# SAM9X75_Pinout.net
KiCad netlist of a schematic drawn in Altium Designer
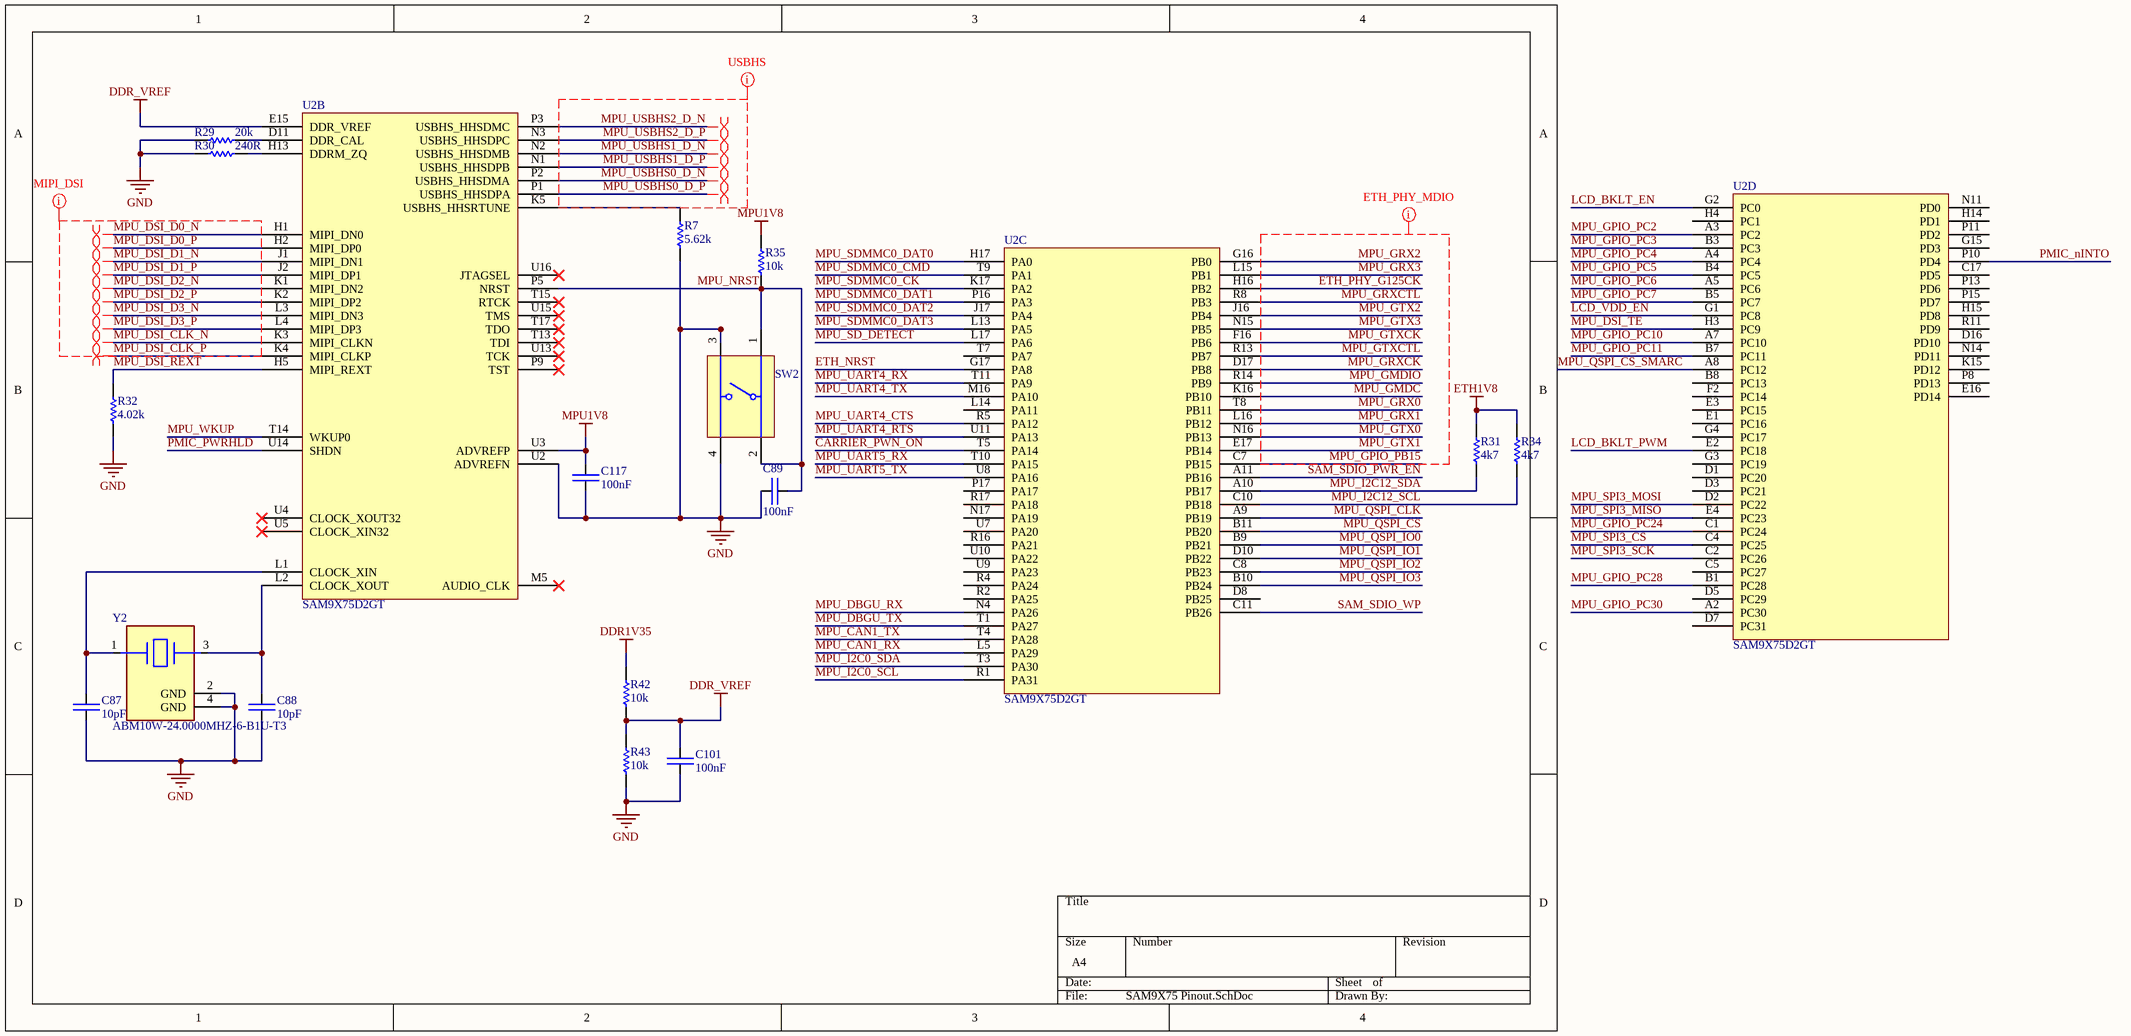
[diagram p0: SAM9X75 Pinout.SchDoc]

(export (version "E")
  (design (tool "Eeschema 10.0.6"))
  (components
    (comp (ref "C87")
      (value "10pF")
      (footprint "CAP-0603")
      (description "Capacitor chip unpolarized. 0603")
      (libsource (lib "Master") (part "CAP-0603"))
    )
    (comp (ref "C88")
      (value "10pF")
      (footprint "CAP-0603")
      (description "Capacitor chip unpolarized. 0603")
      (libsource (lib "Master") (part "CAP-0603"))
    )
    (comp (ref "C89")
      (value "100nF")
      (footprint "CAP-0603")
      (description "Capacitor chip unpolarized. 0603")
      (libsource (lib "Master") (part "CAP-0603"))
    )
    (comp (ref "C101")
      (value "100nF")
      (footprint "CAP-0201")
      (description "Capacitor chip upolarized. 0201")
      (libsource (lib "Master") (part "CAP-0201"))
    )
    (comp (ref "C117")
      (value "100nF")
      (footprint "CAP-0201")
      (description "Capacitor chip upolarized. 0201")
      (libsource (lib "Master") (part "CAP-0201"))
    )
    (comp (ref "R7")
      (value "5.62k")
      (footprint "RES-0201")
      (description "Resistor chip. 0201")
      (libsource (lib "Master") (part "RES-0201"))
    )
    (comp (ref "R29")
      (value "20k")
      (footprint "RES-0201")
      (description "Resistor chip. 0201")
      (libsource (lib "Master") (part "RES-0201"))
    )
    (comp (ref "R30")
      (value "240R")
      (footprint "RES-0201")
      (description "Resistor chip. 0201")
      (libsource (lib "Master") (part "RES-0201"))
    )
    (comp (ref "R31")
      (value "4k7")
      (footprint "RES-0201")
      (description "Resistor chip. 0201")
      (libsource (lib "Master") (part "RES-0201"))
    )
    (comp (ref "R32")
      (value "4.02k")
      (footprint "RES-0201")
      (description "Resistor chip. 0201")
      (libsource (lib "Master") (part "RES-0201"))
    )
    (comp (ref "R34")
      (value "4k7")
      (footprint "RES-0201")
      (description "Resistor chip. 0201")
      (libsource (lib "Master") (part "RES-0201"))
    )
    (comp (ref "R35")
      (value "10k")
      (footprint "RES-0603")
      (description "Resistor chip. 0603")
      (libsource (lib "Master") (part "RES-0603"))
    )
    (comp (ref "R42")
      (value "10k")
      (footprint "RES-0201")
      (description "Resistor chip. 0201")
      (libsource (lib "Master") (part "RES-0201"))
    )
    (comp (ref "R43")
      (value "10k")
      (footprint "RES-0201")
      (description "Resistor chip. 0201")
      (libsource (lib "Master") (part "RES-0201"))
    )
    (comp (ref "SW2")
      (value "FSM4JSMATR")
      (footprint "TECO-FSM4JSMATR_V")
      (description "Micro Miniature Push Button Switch FSM JSM, 50 mA, -35 to 85 degC, 4-Pin SMD, RoHS, Tape and Reel")
      (fields (field (name "MANUFACTURER") "TE Connectivity"))
      (libsource (lib "Altium Content Vault") (part "SW-SPST-4_A"))
    )
    (comp (ref "U2")
      (value "SAM9X75D2GT")
      (footprint "SAM9X75D")
      (description "ARM9 SiP 2GBit Internal DDR3L")
      (libsource (lib "Master") (part "SAM9X75D2GT"))
    )
    (comp (ref "Y2")
      (value "ABM10W-24.0000MHZ-6-B1U-T3")
      (footprint "FP-ABM10W-MFG")
      (description "Crystal 24MHz ±10ppm 6pF SMD-4 2.5mm x 2mm")
      (libsource (lib "Altium Content Vault") (part "5d53a81b36bb19e40e9e80ec3e46f97"))
    )
  )
  (nets
    (net (code "1") (name "/CARRIER_PWN_ON") (class "Default")
      (node (ref "U2") (pin "T5") (pinfunction "PA14_T5") (pintype "passive"))
    )
    (net (code "2") (name "/ETH_NRST") (class "Default")
      (node (ref "U2") (pin "G17") (pinfunction "PA8_G17") (pintype "passive"))
    )
    (net (code "3") (name "/ETH_PHY_G125CK") (class "Default")
      (node (ref "U2") (pin "H16") (pinfunction "PB2_H16") (pintype "passive"))
    )
    (net (code "4") (name "/LCD_BKLT_EN") (class "Default")
      (node (ref "U2") (pin "G2") (pinfunction "PC0_G2") (pintype "passive"))
    )
    (net (code "5") (name "/LCD_BKLT_PWM") (class "Default")
      (node (ref "U2") (pin "E2") (pinfunction "PC18_E2") (pintype "passive"))
    )
    (net (code "6") (name "/LCD_VDD_EN") (class "Default")
      (node (ref "U2") (pin "G1") (pinfunction "PC8_G1") (pintype "passive"))
    )
    (net (code "7") (name "/MPU_CAN1_RX") (class "Default")
      (node (ref "U2") (pin "L5") (pinfunction "PA29_L5") (pintype "passive"))
    )
    (net (code "8") (name "/MPU_CAN1_TX") (class "Default")
      (node (ref "U2") (pin "T4") (pinfunction "PA28_T4") (pintype "passive"))
    )
    (net (code "9") (name "/MPU_DBGU_RX") (class "Default")
      (node (ref "U2") (pin "N4") (pinfunction "PA26_N4") (pintype "passive"))
    )
    (net (code "10") (name "/MPU_DBGU_TX") (class "Default")
      (node (ref "U2") (pin "T1") (pinfunction "PA27_T1") (pintype "passive"))
    )
    (net (code "11") (name "/MPU_DSI_CLK_N") (class "Default")
      (node (ref "U2") (pin "K3") (pinfunction "MIPI_CLKN_K3") (pintype "passive"))
    )
    (net (code "12") (name "/MPU_DSI_CLK_P") (class "Default")
      (node (ref "U2") (pin "K4") (pinfunction "MIPI_CLKP_K4") (pintype "passive"))
    )
    (net (code "13") (name "/MPU_DSI_D0_N") (class "Default")
      (node (ref "U2") (pin "H1") (pinfunction "MIPI_DN0_H1") (pintype "passive"))
    )
    (net (code "14") (name "/MPU_DSI_D0_P") (class "Default")
      (node (ref "U2") (pin "H2") (pinfunction "MIPI_DP0_H2") (pintype "passive"))
    )
    (net (code "15") (name "/MPU_DSI_D1_N") (class "Default")
      (node (ref "U2") (pin "J1") (pinfunction "MIPI_DN1_J1") (pintype "passive"))
    )
    (net (code "16") (name "/MPU_DSI_D1_P") (class "Default")
      (node (ref "U2") (pin "J2") (pinfunction "MIPI_DP1_J2") (pintype "passive"))
    )
    (net (code "17") (name "/MPU_DSI_D2_N") (class "Default")
      (node (ref "U2") (pin "K1") (pinfunction "MIPI_DN2_K1") (pintype "passive"))
    )
    (net (code "18") (name "/MPU_DSI_D2_P") (class "Default")
      (node (ref "U2") (pin "K2") (pinfunction "MIPI_DP2_K2") (pintype "passive"))
    )
    (net (code "19") (name "/MPU_DSI_D3_N") (class "Default")
      (node (ref "U2") (pin "L3") (pinfunction "MIPI_DN3_L3") (pintype "passive"))
    )
    (net (code "20") (name "/MPU_DSI_D3_P") (class "Default")
      (node (ref "U2") (pin "L4") (pinfunction "MIPI_DP3_L4") (pintype "passive"))
    )
    (net (code "21") (name "/MPU_DSI_REXT") (class "Default")
      (node (ref "R32") (pin "2") (pintype "passive"))
      (node (ref "U2") (pin "H5") (pinfunction "MIPI_REXT_H5") (pintype "passive"))
    )
    (net (code "22") (name "/MPU_DSI_TE") (class "Default")
      (node (ref "U2") (pin "H3") (pinfunction "PC9_H3") (pintype "passive"))
    )
    (net (code "23") (name "/MPU_GMDC") (class "Default")
      (node (ref "U2") (pin "K16") (pinfunction "PB10_K16") (pintype "passive"))
    )
    (net (code "24") (name "/MPU_GMDIO") (class "Default")
      (node (ref "U2") (pin "R14") (pinfunction "PB9_R14") (pintype "passive"))
    )
    (net (code "25") (name "/MPU_GPIO_PB15") (class "Default")
      (node (ref "U2") (pin "C7") (pinfunction "PB15_C7") (pintype "passive"))
    )
    (net (code "26") (name "/MPU_GPIO_PC2") (class "Default")
      (node (ref "U2") (pin "A3") (pinfunction "PC2_A3") (pintype "passive"))
    )
    (net (code "27") (name "/MPU_GPIO_PC3") (class "Default")
      (node (ref "U2") (pin "B3") (pinfunction "PC3_B3") (pintype "passive"))
    )
    (net (code "28") (name "/MPU_GPIO_PC4") (class "Default")
      (node (ref "U2") (pin "A4") (pinfunction "PC4_A4") (pintype "passive"))
    )
    (net (code "29") (name "/MPU_GPIO_PC5") (class "Default")
      (node (ref "U2") (pin "B4") (pinfunction "PC5_B4") (pintype "passive"))
    )
    (net (code "30") (name "/MPU_GPIO_PC6") (class "Default")
      (node (ref "U2") (pin "A5") (pinfunction "PC6_A5") (pintype "passive"))
    )
    (net (code "31") (name "/MPU_GPIO_PC7") (class "Default")
      (node (ref "U2") (pin "B5") (pinfunction "PC7_B5") (pintype "passive"))
    )
    (net (code "32") (name "/MPU_GPIO_PC10") (class "Default")
      (node (ref "U2") (pin "A7") (pinfunction "PC10_A7") (pintype "passive"))
    )
    (net (code "33") (name "/MPU_GPIO_PC11") (class "Default")
      (node (ref "U2") (pin "B7") (pinfunction "PC11_B7") (pintype "passive"))
    )
    (net (code "34") (name "/MPU_GPIO_PC24") (class "Default")
      (node (ref "U2") (pin "C1") (pinfunction "PC24_C1") (pintype "passive"))
    )
    (net (code "35") (name "/MPU_GPIO_PC28") (class "Default")
      (node (ref "U2") (pin "B1") (pinfunction "PC28_B1") (pintype "passive"))
    )
    (net (code "36") (name "/MPU_GPIO_PC30") (class "Default")
      (node (ref "U2") (pin "A2") (pinfunction "PC30_A2") (pintype "passive"))
    )
    (net (code "37") (name "/MPU_GRX0") (class "Default")
      (node (ref "U2") (pin "T8") (pinfunction "PB11_T8") (pintype "passive"))
    )
    (net (code "38") (name "/MPU_GRX1") (class "Default")
      (node (ref "U2") (pin "L16") (pinfunction "PB12_L16") (pintype "passive"))
    )
    (net (code "39") (name "/MPU_GRX2") (class "Default")
      (node (ref "U2") (pin "G16") (pinfunction "PB0_G16") (pintype "passive"))
    )
    (net (code "40") (name "/MPU_GRX3") (class "Default")
      (node (ref "U2") (pin "L15") (pinfunction "PB1_L15") (pintype "passive"))
    )
    (net (code "41") (name "/MPU_GRXCK") (class "Default")
      (node (ref "U2") (pin "D17") (pinfunction "PB8_D17") (pintype "passive"))
    )
    (net (code "42") (name "/MPU_GRXCTL") (class "Default")
      (node (ref "U2") (pin "R8") (pinfunction "PB3_R8") (pintype "passive"))
    )
    (net (code "43") (name "/MPU_GTX0") (class "Default")
      (node (ref "U2") (pin "N16") (pinfunction "PB13_N16") (pintype "passive"))
    )
    (net (code "44") (name "/MPU_GTX1") (class "Default")
      (node (ref "U2") (pin "E17") (pinfunction "PB14_E17") (pintype "passive"))
    )
    (net (code "45") (name "/MPU_GTX2") (class "Default")
      (node (ref "U2") (pin "J16") (pinfunction "PB4_J16") (pintype "passive"))
    )
    (net (code "46") (name "/MPU_GTX3") (class "Default")
      (node (ref "U2") (pin "N15") (pinfunction "PB5_N15") (pintype "passive"))
    )
    (net (code "47") (name "/MPU_GTXCK") (class "Default")
      (node (ref "U2") (pin "F16") (pinfunction "PB6_F16") (pintype "passive"))
    )
    (net (code "48") (name "/MPU_GTXCTL") (class "Default")
      (node (ref "U2") (pin "R13") (pinfunction "PB7_R13") (pintype "passive"))
    )
    (net (code "49") (name "/MPU_I2C0_SCL") (class "Default")
      (node (ref "U2") (pin "R1") (pinfunction "PA31_R1") (pintype "passive"))
    )
    (net (code "50") (name "/MPU_I2C0_SDA") (class "Default")
      (node (ref "U2") (pin "T3") (pinfunction "PA30_T3") (pintype "passive"))
    )
    (net (code "51") (name "/MPU_I2C12_SCL") (class "Default")
      (node (ref "R34") (pin "1") (pintype "passive"))
      (node (ref "U2") (pin "C10") (pinfunction "PB18_C10") (pintype "passive"))
    )
    (net (code "52") (name "/MPU_I2C12_SDA") (class "Default")
      (node (ref "R31") (pin "1") (pintype "passive"))
      (node (ref "U2") (pin "A10") (pinfunction "PB17_A10") (pintype "passive"))
    )
    (net (code "53") (name "/MPU_NRST") (class "Default")
      (node (ref "C89") (pin "1") (pintype "passive"))
      (node (ref "R35") (pin "1") (pintype "passive"))
      (node (ref "SW2") (pin "1") (pinfunction "1_1") (pintype "passive"))
      (node (ref "SW2") (pin "2") (pinfunction "2_2") (pintype "passive"))
      (node (ref "U2") (pin "P5") (pinfunction "NRST_P5") (pintype "passive"))
    )
    (net (code "54") (name "/MPU_QSPI_CLK") (class "Default")
      (node (ref "U2") (pin "A9") (pinfunction "PB19_A9") (pintype "passive"))
    )
    (net (code "55") (name "/MPU_QSPI_CS") (class "Default")
      (node (ref "U2") (pin "B11") (pinfunction "PB20_B11") (pintype "passive"))
    )
    (net (code "56") (name "/MPU_QSPI_CS_SMARC") (class "Default")
      (node (ref "U2") (pin "A8") (pinfunction "PC12_A8") (pintype "passive"))
    )
    (net (code "57") (name "/MPU_QSPI_IO0") (class "Default")
      (node (ref "U2") (pin "B9") (pinfunction "PB21_B9") (pintype "passive"))
    )
    (net (code "58") (name "/MPU_QSPI_IO1") (class "Default")
      (node (ref "U2") (pin "D10") (pinfunction "PB22_D10") (pintype "passive"))
    )
    (net (code "59") (name "/MPU_QSPI_IO2") (class "Default")
      (node (ref "U2") (pin "C8") (pinfunction "PB23_C8") (pintype "passive"))
    )
    (net (code "60") (name "/MPU_QSPI_IO3") (class "Default")
      (node (ref "U2") (pin "B10") (pinfunction "PB24_B10") (pintype "passive"))
    )
    (net (code "61") (name "/MPU_SDMMC0_CK") (class "Default")
      (node (ref "U2") (pin "K17") (pinfunction "PA2_K17") (pintype "passive"))
    )
    (net (code "62") (name "/MPU_SDMMC0_CMD") (class "Default")
      (node (ref "U2") (pin "T9") (pinfunction "PA1_T9") (pintype "passive"))
    )
    (net (code "63") (name "/MPU_SDMMC0_DAT0") (class "Default")
      (node (ref "U2") (pin "H17") (pinfunction "PA0_H17") (pintype "passive"))
    )
    (net (code "64") (name "/MPU_SDMMC0_DAT1") (class "Default")
      (node (ref "U2") (pin "P16") (pinfunction "PA3_P16") (pintype "passive"))
    )
    (net (code "65") (name "/MPU_SDMMC0_DAT2") (class "Default")
      (node (ref "U2") (pin "J17") (pinfunction "PA4_J17") (pintype "passive"))
    )
    (net (code "66") (name "/MPU_SDMMC0_DAT3") (class "Default")
      (node (ref "U2") (pin "L13") (pinfunction "PA5_L13") (pintype "passive"))
    )
    (net (code "67") (name "/MPU_SD_DETECT") (class "Default")
      (node (ref "U2") (pin "L17") (pinfunction "PA6_L17") (pintype "passive"))
    )
    (net (code "68") (name "/MPU_SPI3_CS") (class "Default")
      (node (ref "U2") (pin "C4") (pinfunction "PC25_C4") (pintype "passive"))
    )
    (net (code "69") (name "/MPU_SPI3_MISO") (class "Default")
      (node (ref "U2") (pin "E4") (pinfunction "PC23_E4") (pintype "passive"))
    )
    (net (code "70") (name "/MPU_SPI3_MOSI") (class "Default")
      (node (ref "U2") (pin "D2") (pinfunction "PC22_D2") (pintype "passive"))
    )
    (net (code "71") (name "/MPU_SPI3_SCK") (class "Default")
      (node (ref "U2") (pin "C2") (pinfunction "PC26_C2") (pintype "passive"))
    )
    (net (code "72") (name "/MPU_UART4_CTS") (class "Default")
      (node (ref "U2") (pin "R5") (pinfunction "PA12_R5") (pintype "passive"))
    )
    (net (code "73") (name "/MPU_UART4_RTS") (class "Default")
      (node (ref "U2") (pin "U11") (pinfunction "PA13_U11") (pintype "passive"))
    )
    (net (code "74") (name "/MPU_UART4_RX") (class "Default")
      (node (ref "U2") (pin "T11") (pinfunction "PA9_T11") (pintype "passive"))
    )
    (net (code "75") (name "/MPU_UART4_TX") (class "Default")
      (node (ref "U2") (pin "M16") (pinfunction "PA10_M16") (pintype "passive"))
    )
    (net (code "76") (name "/MPU_UART5_RX") (class "Default")
      (node (ref "U2") (pin "T10") (pinfunction "PA15_T10") (pintype "passive"))
    )
    (net (code "77") (name "/MPU_UART5_TX") (class "Default")
      (node (ref "U2") (pin "U8") (pinfunction "PA16_U8") (pintype "passive"))
    )
    (net (code "78") (name "/MPU_USBHS0_D_N") (class "Default")
      (node (ref "U2") (pin "P2") (pinfunction "USBHS_HHSDMA_P2") (pintype "passive"))
    )
    (net (code "79") (name "/MPU_USBHS0_D_P") (class "Default")
      (node (ref "U2") (pin "P1") (pinfunction "USBHS_HHSDPA_P1") (pintype "passive"))
    )
    (net (code "80") (name "/MPU_USBHS1_D_N") (class "Default")
      (node (ref "U2") (pin "N2") (pinfunction "USBHS_HHSDMB_N2") (pintype "passive"))
    )
    (net (code "81") (name "/MPU_USBHS1_D_P") (class "Default")
      (node (ref "U2") (pin "N1") (pinfunction "USBHS_HHSDPB_N1") (pintype "passive"))
    )
    (net (code "82") (name "/MPU_USBHS2_D_N") (class "Default")
      (node (ref "U2") (pin "P3") (pinfunction "USBHS_HHSDMC_P3") (pintype "passive"))
    )
    (net (code "83") (name "/MPU_USBHS2_D_P") (class "Default")
      (node (ref "U2") (pin "N3") (pinfunction "USBHS_HHSDPC_N3") (pintype "passive"))
    )
    (net (code "84") (name "/MPU_WKUP") (class "Default")
      (node (ref "U2") (pin "T14") (pinfunction "WKUP0_T14") (pintype "passive"))
    )
    (net (code "85") (name "/PMIC_PWRHLD") (class "Default")
      (node (ref "U2") (pin "U14") (pinfunction "SHDN_U14") (pintype "passive"))
    )
    (net (code "86") (name "/PMIC_nINTO") (class "Default")
      (node (ref "U2") (pin "P10") (pinfunction "PD4_P10") (pintype "passive"))
    )
    (net (code "87") (name "/SAM_SDIO_PWR_EN") (class "Default")
      (node (ref "U2") (pin "A11") (pinfunction "PB16_A11") (pintype "passive"))
    )
    (net (code "88") (name "/SAM_SDIO_WP") (class "Default")
      (node (ref "U2") (pin "C11") (pinfunction "PB26_C11") (pintype "passive"))
    )
    (net (code "89") (name "DDR1V35") (class "Default") (node (ref "R42") (pin "2") (pintype "passive")))
    (net (code "90") (name "DDR_VREF") (class "Default")
      (node (ref "C101") (pin "2") (pintype "passive"))
      (node (ref "R42") (pin "1") (pintype "passive"))
      (node (ref "R43") (pin "2") (pintype "passive"))
      (node (ref "U2") (pin "E15") (pinfunction "DDR_VREF_E15") (pintype "passive"))
    )
    (net (code "91") (name "ETH1V8") (class "Default")
      (node (ref "R31") (pin "2") (pintype "passive"))
      (node (ref "R34") (pin "2") (pintype "passive"))
    )
    (net (code "92") (name "GND") (class "Default")
      (node (ref "C101") (pin "1") (pintype "passive"))
      (node (ref "C117") (pin "1") (pintype "passive"))
      (node (ref "C87") (pin "1") (pintype "passive"))
      (node (ref "C88") (pin "1") (pintype "passive"))
      (node (ref "C89") (pin "2") (pintype "passive"))
      (node (ref "R29") (pin "1") (pintype "passive"))
      (node (ref "R30") (pin "1") (pintype "passive"))
      (node (ref "R32") (pin "1") (pintype "passive"))
      (node (ref "R43") (pin "1") (pintype "passive"))
      (node (ref "R7") (pin "1") (pintype "passive"))
      (node (ref "SW2") (pin "3") (pinfunction "3_3") (pintype "passive"))
      (node (ref "SW2") (pin "4") (pinfunction "4_4") (pintype "passive"))
      (node (ref "U2") (pin "U2") (pinfunction "ADVREFN_U2") (pintype "passive"))
      (node (ref "Y2") (pin "2") (pinfunction "GND_2") (pintype "power_in"))
      (node (ref "Y2") (pin "4") (pinfunction "GND_4") (pintype "power_in"))
    )
    (net (code "93") (name "MPU1V8") (class "Default")
      (node (ref "C117") (pin "2") (pintype "passive"))
      (node (ref "R35") (pin "2") (pintype "passive"))
      (node (ref "U2") (pin "U3") (pinfunction "ADVREFP_U3") (pintype "passive"))
    )
    (net (code "94") (name "Net-(U2B-CLOCK_XIN)") (class "Default")
      (node (ref "C87") (pin "2") (pintype "passive"))
      (node (ref "U2") (pin "L1") (pinfunction "CLOCK_XIN_L1") (pintype "passive"))
      (node (ref "Y2") (pin "1") (pinfunction "1_1") (pintype "passive"))
    )
    (net (code "95") (name "Net-(U2B-CLOCK_XOUT)") (class "Default")
      (node (ref "C88") (pin "2") (pintype "passive"))
      (node (ref "U2") (pin "L2") (pinfunction "CLOCK_XOUT_L2") (pintype "passive"))
      (node (ref "Y2") (pin "3") (pinfunction "3_3") (pintype "passive"))
    )
    (net (code "96") (name "Net-(U2B-DDRM_ZQ)") (class "Default")
      (node (ref "R30") (pin "2") (pintype "passive"))
      (node (ref "U2") (pin "H13") (pinfunction "DDRM_ZQ_H13") (pintype "passive"))
    )
    (net (code "97") (name "Net-(U2B-DDR_CAL)") (class "Default")
      (node (ref "R29") (pin "2") (pintype "passive"))
      (node (ref "U2") (pin "D11") (pinfunction "DDR_CAL_D11") (pintype "passive"))
    )
    (net (code "98") (name "Net-(U2B-USBHS_HHSRTUNE)") (class "Default")
      (node (ref "R7") (pin "2") (pintype "passive"))
      (node (ref "U2") (pin "K5") (pinfunction "USBHS_HHSRTUNE_K5") (pintype "passive"))
    )
    (net (code "99") (name "unconnected-(U2B-AUDIO_CLK-PadM5)") (class "Default")
      (node (ref "U2") (pin "M5") (pinfunction "AUDIO_CLK_M5") (pintype "passive+no_connect"))
    )
    (net (code "100") (name "unconnected-(U2B-CLOCK_XIN32-PadU5)") (class "Default")
      (node (ref "U2") (pin "U5") (pinfunction "CLOCK_XIN32_U5") (pintype "passive+no_connect"))
    )
    (net (code "101") (name "unconnected-(U2B-CLOCK_XOUT32-PadU4)") (class "Default")
      (node (ref "U2") (pin "U4") (pinfunction "CLOCK_XOUT32_U4") (pintype "passive+no_connect"))
    )
    (net (code "102") (name "unconnected-(U2B-JTAGSEL-PadU16)") (class "Default")
      (node (ref "U2") (pin "U16") (pinfunction "JTAGSEL_U16") (pintype "passive+no_connect"))
    )
    (net (code "103") (name "unconnected-(U2B-RTCK-PadT15)") (class "Default")
      (node (ref "U2") (pin "T15") (pinfunction "RTCK_T15") (pintype "passive+no_connect"))
    )
    (net (code "104") (name "unconnected-(U2B-TCK-PadU13)") (class "Default")
      (node (ref "U2") (pin "U13") (pinfunction "TCK_U13") (pintype "passive+no_connect"))
    )
    (net (code "105") (name "unconnected-(U2B-TDI-PadT13)") (class "Default")
      (node (ref "U2") (pin "T13") (pinfunction "TDI_T13") (pintype "passive+no_connect"))
    )
    (net (code "106") (name "unconnected-(U2B-TDO-PadT17)") (class "Default")
      (node (ref "U2") (pin "T17") (pinfunction "TDO_T17") (pintype "passive+no_connect"))
    )
    (net (code "107") (name "unconnected-(U2B-TMS-PadU15)") (class "Default")
      (node (ref "U2") (pin "U15") (pinfunction "TMS_U15") (pintype "passive+no_connect"))
    )
    (net (code "108") (name "unconnected-(U2B-TST-PadP9)") (class "Default")
      (node (ref "U2") (pin "P9") (pinfunction "TST_P9") (pintype "passive+no_connect"))
    )
    (net (code "109") (name "unconnected-(U2C-PA7-PadT7)") (class "Default")
      (node (ref "U2") (pin "T7") (pinfunction "PA7_T7") (pintype "passive"))
    )
    (net (code "110") (name "unconnected-(U2C-PA11-PadL14)") (class "Default")
      (node (ref "U2") (pin "L14") (pinfunction "PA11_L14") (pintype "passive"))
    )
    (net (code "111") (name "unconnected-(U2C-PA17-PadP17)") (class "Default")
      (node (ref "U2") (pin "P17") (pinfunction "PA17_P17") (pintype "passive"))
    )
    (net (code "112") (name "unconnected-(U2C-PA18-PadR17)") (class "Default")
      (node (ref "U2") (pin "R17") (pinfunction "PA18_R17") (pintype "passive"))
    )
    (net (code "113") (name "unconnected-(U2C-PA19-PadN17)") (class "Default")
      (node (ref "U2") (pin "N17") (pinfunction "PA19_N17") (pintype "passive"))
    )
    (net (code "114") (name "unconnected-(U2C-PA20-PadU7)") (class "Default")
      (node (ref "U2") (pin "U7") (pinfunction "PA20_U7") (pintype "passive"))
    )
    (net (code "115") (name "unconnected-(U2C-PA21-PadR16)") (class "Default")
      (node (ref "U2") (pin "R16") (pinfunction "PA21_R16") (pintype "passive"))
    )
    (net (code "116") (name "unconnected-(U2C-PA22-PadU10)") (class "Default")
      (node (ref "U2") (pin "U10") (pinfunction "PA22_U10") (pintype "passive"))
    )
    (net (code "117") (name "unconnected-(U2C-PA23-PadU9)") (class "Default")
      (node (ref "U2") (pin "U9") (pinfunction "PA23_U9") (pintype "passive"))
    )
    (net (code "118") (name "unconnected-(U2C-PA24-PadR4)") (class "Default")
      (node (ref "U2") (pin "R4") (pinfunction "PA24_R4") (pintype "passive"))
    )
    (net (code "119") (name "unconnected-(U2C-PA25-PadR2)") (class "Default")
      (node (ref "U2") (pin "R2") (pinfunction "PA25_R2") (pintype "passive"))
    )
    (net (code "120") (name "unconnected-(U2C-PB25-PadD8)") (class "Default")
      (node (ref "U2") (pin "D8") (pinfunction "PB25_D8") (pintype "passive"))
    )
    (net (code "121") (name "unconnected-(U2D-PC1-PadH4)") (class "Default")
      (node (ref "U2") (pin "H4") (pinfunction "PC1_H4") (pintype "passive"))
    )
    (net (code "122") (name "unconnected-(U2D-PC13-PadB8)") (class "Default")
      (node (ref "U2") (pin "B8") (pinfunction "PC13_B8") (pintype "passive"))
    )
    (net (code "123") (name "unconnected-(U2D-PC14-PadF2)") (class "Default")
      (node (ref "U2") (pin "F2") (pinfunction "PC14_F2") (pintype "passive"))
    )
    (net (code "124") (name "unconnected-(U2D-PC15-PadE3)") (class "Default")
      (node (ref "U2") (pin "E3") (pinfunction "PC15_E3") (pintype "passive"))
    )
    (net (code "125") (name "unconnected-(U2D-PC16-PadE1)") (class "Default")
      (node (ref "U2") (pin "E1") (pinfunction "PC16_E1") (pintype "passive"))
    )
    (net (code "126") (name "unconnected-(U2D-PC17-PadG4)") (class "Default")
      (node (ref "U2") (pin "G4") (pinfunction "PC17_G4") (pintype "passive"))
    )
    (net (code "127") (name "unconnected-(U2D-PC19-PadG3)") (class "Default")
      (node (ref "U2") (pin "G3") (pinfunction "PC19_G3") (pintype "passive"))
    )
    (net (code "128") (name "unconnected-(U2D-PC20-PadD1)") (class "Default")
      (node (ref "U2") (pin "D1") (pinfunction "PC20_D1") (pintype "passive"))
    )
    (net (code "129") (name "unconnected-(U2D-PC21-PadD3)") (class "Default")
      (node (ref "U2") (pin "D3") (pinfunction "PC21_D3") (pintype "passive"))
    )
    (net (code "130") (name "unconnected-(U2D-PC27-PadC5)") (class "Default")
      (node (ref "U2") (pin "C5") (pinfunction "PC27_C5") (pintype "passive"))
    )
    (net (code "131") (name "unconnected-(U2D-PC29-PadD5)") (class "Default")
      (node (ref "U2") (pin "D5") (pinfunction "PC29_D5") (pintype "passive"))
    )
    (net (code "132") (name "unconnected-(U2D-PC31-PadD7)") (class "Default")
      (node (ref "U2") (pin "D7") (pinfunction "PC31_D7") (pintype "passive"))
    )
    (net (code "133") (name "unconnected-(U2D-PD0-PadN11)") (class "Default")
      (node (ref "U2") (pin "N11") (pinfunction "PD0_N11") (pintype "passive"))
    )
    (net (code "134") (name "unconnected-(U2D-PD1-PadH14)") (class "Default")
      (node (ref "U2") (pin "H14") (pinfunction "PD1_H14") (pintype "passive"))
    )
    (net (code "135") (name "unconnected-(U2D-PD2-PadP11)") (class "Default")
      (node (ref "U2") (pin "P11") (pinfunction "PD2_P11") (pintype "passive"))
    )
    (net (code "136") (name "unconnected-(U2D-PD3-PadG15)") (class "Default")
      (node (ref "U2") (pin "G15") (pinfunction "PD3_G15") (pintype "passive"))
    )
    (net (code "137") (name "unconnected-(U2D-PD5-PadC17)") (class "Default")
      (node (ref "U2") (pin "C17") (pinfunction "PD5_C17") (pintype "passive"))
    )
    (net (code "138") (name "unconnected-(U2D-PD6-PadP13)") (class "Default")
      (node (ref "U2") (pin "P13") (pinfunction "PD6_P13") (pintype "passive"))
    )
    (net (code "139") (name "unconnected-(U2D-PD7-PadP15)") (class "Default")
      (node (ref "U2") (pin "P15") (pinfunction "PD7_P15") (pintype "passive"))
    )
    (net (code "140") (name "unconnected-(U2D-PD8-PadH15)") (class "Default")
      (node (ref "U2") (pin "H15") (pinfunction "PD8_H15") (pintype "passive"))
    )
    (net (code "141") (name "unconnected-(U2D-PD9-PadR11)") (class "Default")
      (node (ref "U2") (pin "R11") (pinfunction "PD9_R11") (pintype "passive"))
    )
    (net (code "142") (name "unconnected-(U2D-PD10-PadD16)") (class "Default")
      (node (ref "U2") (pin "D16") (pinfunction "PD10_D16") (pintype "passive"))
    )
    (net (code "143") (name "unconnected-(U2D-PD11-PadN14)") (class "Default")
      (node (ref "U2") (pin "N14") (pinfunction "PD11_N14") (pintype "passive"))
    )
    (net (code "144") (name "unconnected-(U2D-PD12-PadK15)") (class "Default")
      (node (ref "U2") (pin "K15") (pinfunction "PD12_K15") (pintype "passive"))
    )
    (net (code "145") (name "unconnected-(U2D-PD13-PadP8)") (class "Default")
      (node (ref "U2") (pin "P8") (pinfunction "PD13_P8") (pintype "passive"))
    )
    (net (code "146") (name "unconnected-(U2D-PD14-PadE16)") (class "Default")
      (node (ref "U2") (pin "E16") (pinfunction "PD14_E16") (pintype "passive"))
    )
  )
)
